# MainMemory.net
KiCad netlist of a schematic drawn in EAGLE
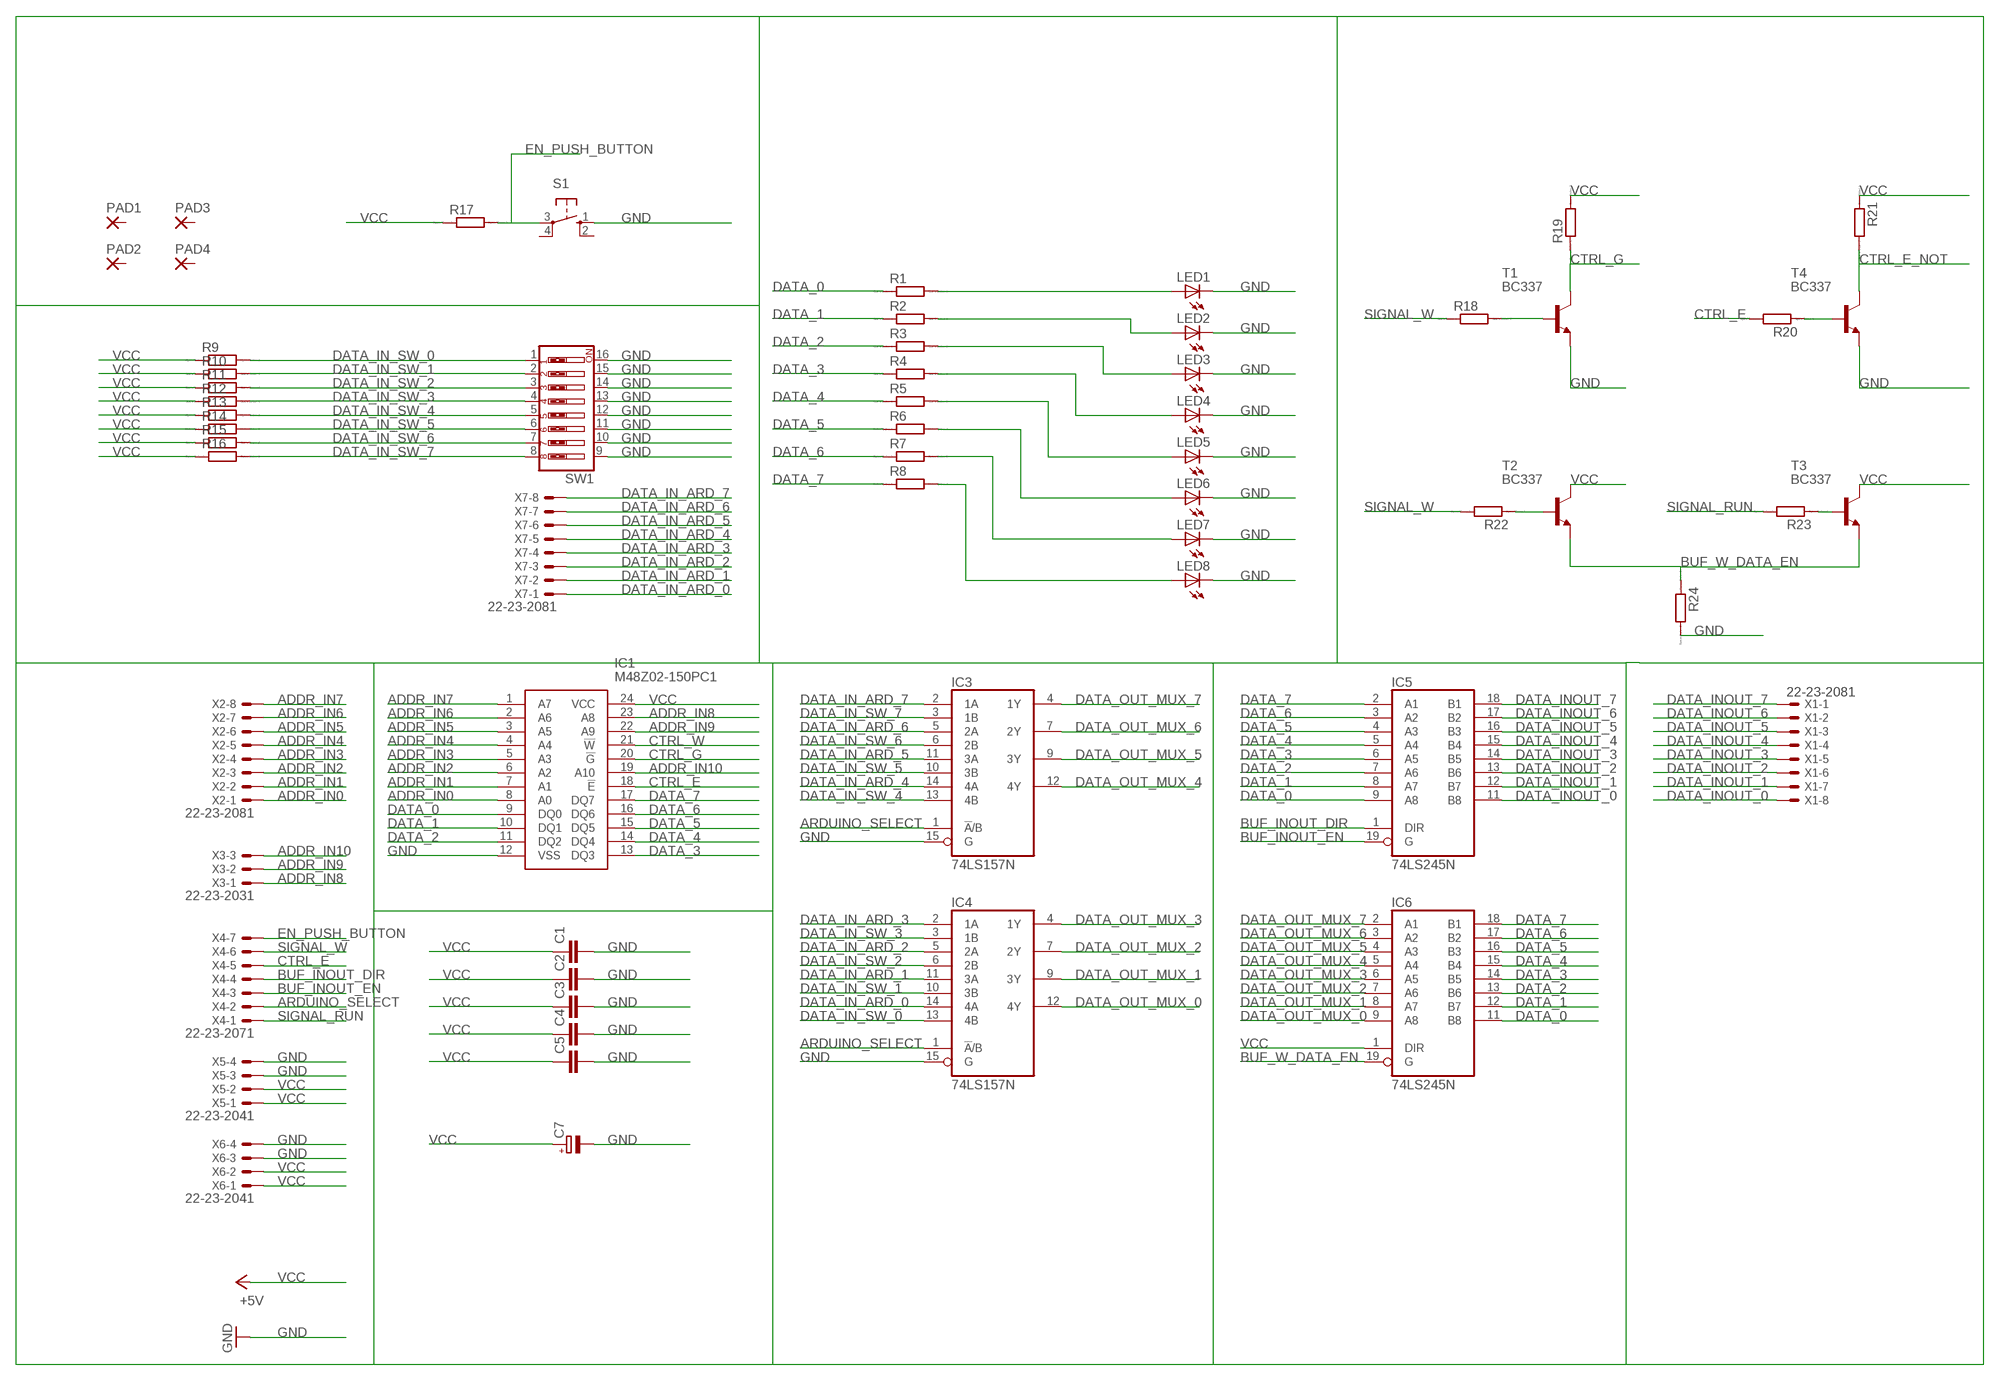
[diagram p0: schematic, sheet 1]

(export (version "E")
  (design (tool "Eeschema 10.0.6"))
  (components
    (comp (ref "C1")
      (value "C-EU025-025X050")
      (footprint "eagle-import:C025-025X050")
      (libsource (lib "eagle-import") (part "C-EU025-025X050"))
    )
    (comp (ref "C2")
      (value "C-EU025-025X050")
      (footprint "eagle-import:C025-025X050")
      (libsource (lib "eagle-import") (part "C-EU025-025X050"))
    )
    (comp (ref "C3")
      (value "C-EU025-025X050")
      (footprint "eagle-import:C025-025X050")
      (libsource (lib "eagle-import") (part "C-EU025-025X050"))
    )
    (comp (ref "C4")
      (value "C-EU025-025X050")
      (footprint "eagle-import:C025-025X050")
      (libsource (lib "eagle-import") (part "C-EU025-025X050"))
    )
    (comp (ref "C5")
      (value "C-EU025-025X050")
      (footprint "eagle-import:C025-025X050")
      (libsource (lib "eagle-import") (part "C-EU025-025X050"))
    )
    (comp (ref "C7")
      (value "CPOL-EUE2.5-6")
      (footprint "eagle-import:E2,5-6")
      (libsource (lib "eagle-import") (part "CPOL-EUE2.5-6"))
    )
    (comp (ref "IC1")
      (value "M48Z02-150PC1")
      (footprint "eagle-import:DIP1562W53P279L3454H965Q24N")
      (fields (field (name "MOUSER_PART_NUMBER") "511-M48Z0215PC1") (field (name "RS_PART_NUMBER") "8289958"))
      (libsource (lib "eagle-import") (part "M48Z02-150PC1"))
    )
    (comp (ref "IC3")
      (value "74LS157N")
      (footprint "eagle-import:DIL16")
      (libsource (lib "eagle-import") (part "74157NLS"))
    )
    (comp (ref "IC4")
      (value "74LS157N")
      (footprint "eagle-import:DIL16")
      (libsource (lib "eagle-import") (part "74157NLS"))
    )
    (comp (ref "IC5")
      (value "74LS245N")
      (footprint "eagle-import:DIL20")
      (libsource (lib "eagle-import") (part "74245NLS"))
    )
    (comp (ref "IC6")
      (value "74LS245N")
      (footprint "eagle-import:DIL20")
      (libsource (lib "eagle-import") (part "74245NLS"))
    )
    (comp (ref "LED1")
      (value "LED5MM")
      (footprint "eagle-import:LED5MM")
      (libsource (lib "eagle-import") (part "LED5MM"))
    )
    (comp (ref "LED2")
      (value "LED5MM")
      (footprint "eagle-import:LED5MM")
      (libsource (lib "eagle-import") (part "LED5MM"))
    )
    (comp (ref "LED3")
      (value "LED5MM")
      (footprint "eagle-import:LED5MM")
      (libsource (lib "eagle-import") (part "LED5MM"))
    )
    (comp (ref "LED4")
      (value "LED5MM")
      (footprint "eagle-import:LED5MM")
      (libsource (lib "eagle-import") (part "LED5MM"))
    )
    (comp (ref "LED5")
      (value "LED5MM")
      (footprint "eagle-import:LED5MM")
      (libsource (lib "eagle-import") (part "LED5MM"))
    )
    (comp (ref "LED6")
      (value "LED5MM")
      (footprint "eagle-import:LED5MM")
      (libsource (lib "eagle-import") (part "LED5MM"))
    )
    (comp (ref "LED7")
      (value "LED5MM")
      (footprint "eagle-import:LED5MM")
      (libsource (lib "eagle-import") (part "LED5MM"))
    )
    (comp (ref "LED8")
      (value "LED5MM")
      (footprint "eagle-import:LED5MM")
      (libsource (lib "eagle-import") (part "LED5MM"))
    )
    (comp (ref "PAD1")
      (value "3,17/1,3")
      (footprint "eagle-import:3,17_1,3")
      (libsource (lib "eagle-import") (part "3,17/1,3"))
    )
    (comp (ref "PAD2")
      (value "3,17/1,3")
      (footprint "eagle-import:3,17_1,3")
      (libsource (lib "eagle-import") (part "3,17/1,3"))
    )
    (comp (ref "PAD3")
      (value "3,17/1,3")
      (footprint "eagle-import:3,17_1,3")
      (libsource (lib "eagle-import") (part "3,17/1,3"))
    )
    (comp (ref "PAD4")
      (value "3,17/1,3")
      (footprint "eagle-import:3,17_1,3")
      (libsource (lib "eagle-import") (part "3,17/1,3"))
    )
    (comp (ref "R1")
      (value "R0207/10")
      (footprint "eagle-import:0207_10")
      (libsource (lib "eagle-import") (part "R0207/10"))
    )
    (comp (ref "R2")
      (value "R0207/10")
      (footprint "eagle-import:0207_10")
      (libsource (lib "eagle-import") (part "R0207/10"))
    )
    (comp (ref "R3")
      (value "R0207/10")
      (footprint "eagle-import:0207_10")
      (libsource (lib "eagle-import") (part "R0207/10"))
    )
    (comp (ref "R4")
      (value "R0207/10")
      (footprint "eagle-import:0207_10")
      (libsource (lib "eagle-import") (part "R0207/10"))
    )
    (comp (ref "R5")
      (value "R0207/10")
      (footprint "eagle-import:0207_10")
      (libsource (lib "eagle-import") (part "R0207/10"))
    )
    (comp (ref "R6")
      (value "R0207/10")
      (footprint "eagle-import:0207_10")
      (libsource (lib "eagle-import") (part "R0207/10"))
    )
    (comp (ref "R7")
      (value "R0207/10")
      (footprint "eagle-import:0207_10")
      (libsource (lib "eagle-import") (part "R0207/10"))
    )
    (comp (ref "R8")
      (value "R0207/10")
      (footprint "eagle-import:0207_10")
      (libsource (lib "eagle-import") (part "R0207/10"))
    )
    (comp (ref "R9")
      (value "R0207/10")
      (footprint "eagle-import:0207_10")
      (libsource (lib "eagle-import") (part "R0207/10"))
    )
    (comp (ref "R10")
      (value "R0207/10")
      (footprint "eagle-import:0207_10")
      (libsource (lib "eagle-import") (part "R0207/10"))
    )
    (comp (ref "R11")
      (value "R0207/10")
      (footprint "eagle-import:0207_10")
      (libsource (lib "eagle-import") (part "R0207/10"))
    )
    (comp (ref "R12")
      (value "R0207/10")
      (footprint "eagle-import:0207_10")
      (libsource (lib "eagle-import") (part "R0207/10"))
    )
    (comp (ref "R13")
      (value "R0207/10")
      (footprint "eagle-import:0207_10")
      (libsource (lib "eagle-import") (part "R0207/10"))
    )
    (comp (ref "R14")
      (value "R0207/10")
      (footprint "eagle-import:0207_10")
      (libsource (lib "eagle-import") (part "R0207/10"))
    )
    (comp (ref "R15")
      (value "R0207/10")
      (footprint "eagle-import:0207_10")
      (libsource (lib "eagle-import") (part "R0207/10"))
    )
    (comp (ref "R16")
      (value "R0207/10")
      (footprint "eagle-import:0207_10")
      (libsource (lib "eagle-import") (part "R0207/10"))
    )
    (comp (ref "R17")
      (value "R0207/10")
      (footprint "eagle-import:0207_10")
      (libsource (lib "eagle-import") (part "R0207/10"))
    )
    (comp (ref "R18")
      (value "R0207/10")
      (footprint "eagle-import:0207_10")
      (libsource (lib "eagle-import") (part "R0207/10"))
    )
    (comp (ref "R19")
      (value "R0207/10")
      (footprint "eagle-import:0207_10")
      (libsource (lib "eagle-import") (part "R0207/10"))
    )
    (comp (ref "R20")
      (value "R0207/10")
      (footprint "eagle-import:0207_10")
      (libsource (lib "eagle-import") (part "R0207/10"))
    )
    (comp (ref "R21")
      (value "R0207/10")
      (footprint "eagle-import:0207_10")
      (libsource (lib "eagle-import") (part "R0207/10"))
    )
    (comp (ref "R22")
      (value "R0207/10")
      (footprint "eagle-import:0207_10")
      (libsource (lib "eagle-import") (part "R0207/10"))
    )
    (comp (ref "R23")
      (value "R0207/10")
      (footprint "eagle-import:0207_10")
      (libsource (lib "eagle-import") (part "R0207/10"))
    )
    (comp (ref "R24")
      (value "R0207/10")
      (footprint "eagle-import:0207_10")
      (libsource (lib "eagle-import") (part "R0207/10"))
    )
    (comp (ref "S1")
      (value "10-XX")
      (footprint "eagle-import:B3F-10XX")
      (fields (field (name "MPN") "B3F-1000"))
      (libsource (lib "eagle-import") (part "10-XX"))
    )
    (comp (ref "SW1")
      (value "SW_DIP-8")
      (footprint "eagle-import:EDG-08")
      (libsource (lib "eagle-import") (part "SW_DIP-8"))
    )
    (comp (ref "T1")
      (value "BC337")
      (footprint "eagle-import:TO92")
      (libsource (lib "eagle-import") (part "BC337"))
    )
    (comp (ref "T2")
      (value "BC337")
      (footprint "eagle-import:TO92")
      (libsource (lib "eagle-import") (part "BC337"))
    )
    (comp (ref "T3")
      (value "BC337")
      (footprint "eagle-import:TO92")
      (libsource (lib "eagle-import") (part "BC337"))
    )
    (comp (ref "T4")
      (value "BC337")
      (footprint "eagle-import:TO92")
      (libsource (lib "eagle-import") (part "BC337"))
    )
    (comp (ref "X1")
      (value "22-23-2081")
      (footprint "eagle-import:22-23-2081")
      (fields (field (name "MF") "MOLEX"))
      (libsource (lib "eagle-import") (part "22-23-2081"))
    )
    (comp (ref "X2")
      (value "22-23-2081")
      (footprint "eagle-import:22-23-2081")
      (fields (field (name "MF") "MOLEX"))
      (libsource (lib "eagle-import") (part "22-23-2081"))
    )
    (comp (ref "X3")
      (value "22-23-2031")
      (footprint "eagle-import:22-23-2031")
      (fields (field (name "MF") "MOLEX"))
      (libsource (lib "eagle-import") (part "22-23-2031"))
    )
    (comp (ref "X4")
      (value "22-23-2071")
      (footprint "eagle-import:22-23-2071")
      (fields (field (name "MF") "MOLEX"))
      (libsource (lib "eagle-import") (part "22-23-2071"))
    )
    (comp (ref "X5")
      (value "22-23-2041")
      (footprint "eagle-import:22-23-2041")
      (fields (field (name "MF") "MOLEX"))
      (libsource (lib "eagle-import") (part "22-23-2041"))
    )
    (comp (ref "X6")
      (value "22-23-2041")
      (footprint "eagle-import:22-23-2041")
      (fields (field (name "MF") "MOLEX"))
      (libsource (lib "eagle-import") (part "22-23-2041"))
    )
    (comp (ref "X7")
      (value "22-23-2081")
      (footprint "eagle-import:22-23-2081")
      (fields (field (name "MF") "MOLEX"))
      (libsource (lib "eagle-import") (part "22-23-2081"))
    )
  )
  (nets
    (net (code "1") (name "+5V") (class "Default")
      (node (ref "C1") (pin "1") (pinfunction "1_1") (pintype "passive"))
      (node (ref "C2") (pin "1") (pinfunction "1_1") (pintype "passive"))
      (node (ref "C3") (pin "1") (pinfunction "1_1") (pintype "passive"))
      (node (ref "C4") (pin "1") (pinfunction "1_1") (pintype "passive"))
      (node (ref "C5") (pin "1") (pinfunction "1_1") (pintype "passive"))
      (node (ref "C7") (pin "+") (pinfunction "+_+") (pintype "passive"))
      (node (ref "IC1") (pin "24") (pinfunction "VCC_24") (pintype "power_in"))
      (node (ref "IC6") (pin "1") (pinfunction "DIR_1") (pintype "input"))
      (node (ref "R10") (pin "1") (pinfunction "1_1") (pintype "passive"))
      (node (ref "R11") (pin "1") (pinfunction "1_1") (pintype "passive"))
      (node (ref "R12") (pin "1") (pinfunction "1_1") (pintype "passive"))
      (node (ref "R13") (pin "1") (pinfunction "1_1") (pintype "passive"))
      (node (ref "R14") (pin "1") (pinfunction "1_1") (pintype "passive"))
      (node (ref "R15") (pin "1") (pinfunction "1_1") (pintype "passive"))
      (node (ref "R16") (pin "1") (pinfunction "1_1") (pintype "passive"))
      (node (ref "R17") (pin "1") (pinfunction "1_1") (pintype "passive"))
      (node (ref "R19") (pin "2") (pinfunction "2_2") (pintype "passive"))
      (node (ref "R21") (pin "1") (pinfunction "1_1") (pintype "passive"))
      (node (ref "R9") (pin "1") (pinfunction "1_1") (pintype "passive"))
      (node (ref "T2") (pin "3") (pinfunction "C_3") (pintype "passive"))
      (node (ref "T3") (pin "3") (pinfunction "C_3") (pintype "passive"))
      (node (ref "X5") (pin "1") (pinfunction "S_1") (pintype "passive"))
      (node (ref "X5") (pin "2") (pinfunction "S_2") (pintype "passive"))
      (node (ref "X6") (pin "1") (pinfunction "S_1") (pintype "passive"))
      (node (ref "X6") (pin "2") (pinfunction "S_2") (pintype "passive"))
    )
    (net (code "2") (name "/ADDR_IN0") (class "Default")
      (node (ref "IC1") (pin "8") (pinfunction "A0_8") (pintype "bidirectional"))
      (node (ref "X2") (pin "1") (pinfunction "S_1") (pintype "passive"))
    )
    (net (code "3") (name "/ADDR_IN1") (class "Default")
      (node (ref "IC1") (pin "7") (pinfunction "A1_7") (pintype "bidirectional"))
      (node (ref "X2") (pin "2") (pinfunction "S_2") (pintype "passive"))
    )
    (net (code "4") (name "/ADDR_IN2") (class "Default")
      (node (ref "IC1") (pin "6") (pinfunction "A2_6") (pintype "bidirectional"))
      (node (ref "X2") (pin "3") (pinfunction "S_3") (pintype "passive"))
    )
    (net (code "5") (name "/ADDR_IN3") (class "Default")
      (node (ref "IC1") (pin "5") (pinfunction "A3_5") (pintype "bidirectional"))
      (node (ref "X2") (pin "4") (pinfunction "S_4") (pintype "passive"))
    )
    (net (code "6") (name "/ADDR_IN4") (class "Default")
      (node (ref "IC1") (pin "4") (pinfunction "A4_4") (pintype "bidirectional"))
      (node (ref "X2") (pin "5") (pinfunction "S_5") (pintype "passive"))
    )
    (net (code "7") (name "/ADDR_IN5") (class "Default")
      (node (ref "IC1") (pin "3") (pinfunction "A5_3") (pintype "bidirectional"))
      (node (ref "X2") (pin "6") (pinfunction "S_6") (pintype "passive"))
    )
    (net (code "8") (name "/ADDR_IN6") (class "Default")
      (node (ref "IC1") (pin "2") (pinfunction "A6_2") (pintype "bidirectional"))
      (node (ref "X2") (pin "7") (pinfunction "S_7") (pintype "passive"))
    )
    (net (code "9") (name "/ADDR_IN7") (class "Default")
      (node (ref "IC1") (pin "1") (pinfunction "A7_1") (pintype "bidirectional"))
      (node (ref "X2") (pin "8") (pinfunction "S_8") (pintype "passive"))
    )
    (net (code "10") (name "/ADDR_IN8") (class "Default")
      (node (ref "IC1") (pin "23") (pinfunction "A8_23") (pintype "bidirectional"))
      (node (ref "X3") (pin "1") (pinfunction "S_1") (pintype "passive"))
    )
    (net (code "11") (name "/ADDR_IN9") (class "Default")
      (node (ref "IC1") (pin "22") (pinfunction "A9_22") (pintype "bidirectional"))
      (node (ref "X3") (pin "2") (pinfunction "S_2") (pintype "passive"))
    )
    (net (code "12") (name "/ADDR_IN10") (class "Default")
      (node (ref "IC1") (pin "19") (pinfunction "A10_19") (pintype "bidirectional"))
      (node (ref "X3") (pin "3") (pinfunction "S_3") (pintype "passive"))
    )
    (net (code "13") (name "/ARDUINO_SELECT") (class "Default")
      (node (ref "IC3") (pin "1") (pinfunction "~{A}/B_1") (pintype "input"))
      (node (ref "IC4") (pin "1") (pinfunction "~{A}/B_1") (pintype "input"))
      (node (ref "X4") (pin "2") (pinfunction "S_2") (pintype "passive"))
    )
    (net (code "14") (name "/BUF_INOUT_DIR") (class "Default")
      (node (ref "IC5") (pin "1") (pinfunction "DIR_1") (pintype "input"))
      (node (ref "X4") (pin "4") (pinfunction "S_4") (pintype "passive"))
    )
    (net (code "15") (name "/BUF_INOUT_EN") (class "Default")
      (node (ref "IC5") (pin "19") (pinfunction "G_19") (pintype "input"))
      (node (ref "X4") (pin "3") (pinfunction "S_3") (pintype "passive"))
    )
    (net (code "16") (name "/BUF_W_DATA_EN") (class "Default")
      (node (ref "IC6") (pin "19") (pinfunction "G_19") (pintype "input"))
      (node (ref "R24") (pin "1") (pinfunction "1_1") (pintype "passive"))
      (node (ref "T2") (pin "1") (pinfunction "E_1") (pintype "passive"))
      (node (ref "T3") (pin "1") (pinfunction "E_1") (pintype "passive"))
    )
    (net (code "17") (name "/CTRL_E") (class "Default")
      (node (ref "IC1") (pin "18") (pinfunction "~{E}_18") (pintype "bidirectional"))
      (node (ref "R20") (pin "2") (pinfunction "2_2") (pintype "passive"))
      (node (ref "X4") (pin "5") (pinfunction "S_5") (pintype "passive"))
    )
    (net (code "18") (name "/CTRL_E_NOT") (class "Default")
      (node (ref "R21") (pin "2") (pinfunction "2_2") (pintype "passive"))
      (node (ref "T4") (pin "3") (pinfunction "C_3") (pintype "passive"))
    )
    (net (code "19") (name "/CTRL_G") (class "Default")
      (node (ref "IC1") (pin "20") (pinfunction "~{G}_20") (pintype "bidirectional"))
      (node (ref "R19") (pin "1") (pinfunction "1_1") (pintype "passive"))
      (node (ref "T1") (pin "3") (pinfunction "C_3") (pintype "passive"))
    )
    (net (code "20") (name "/CTRL_W") (class "Default")
      (node (ref "IC1") (pin "21") (pinfunction "~{W}_21") (pintype "bidirectional"))
    )
    (net (code "21") (name "/DATA_0") (class "Default")
      (node (ref "IC1") (pin "9") (pinfunction "DQ0_9") (pintype "bidirectional"))
      (node (ref "IC5") (pin "9") (pinfunction "A8_9") (pintype "bidirectional"))
      (node (ref "IC6") (pin "11") (pinfunction "B8_11") (pintype "bidirectional"))
      (node (ref "R1") (pin "1") (pinfunction "1_1") (pintype "passive"))
    )
    (net (code "22") (name "/DATA_1") (class "Default")
      (node (ref "IC1") (pin "10") (pinfunction "DQ1_10") (pintype "bidirectional"))
      (node (ref "IC5") (pin "8") (pinfunction "A7_8") (pintype "bidirectional"))
      (node (ref "IC6") (pin "12") (pinfunction "B7_12") (pintype "bidirectional"))
      (node (ref "R2") (pin "1") (pinfunction "1_1") (pintype "passive"))
    )
    (net (code "23") (name "/DATA_2") (class "Default")
      (node (ref "IC1") (pin "11") (pinfunction "DQ2_11") (pintype "bidirectional"))
      (node (ref "IC5") (pin "7") (pinfunction "A6_7") (pintype "bidirectional"))
      (node (ref "IC6") (pin "13") (pinfunction "B6_13") (pintype "bidirectional"))
      (node (ref "R3") (pin "1") (pinfunction "1_1") (pintype "passive"))
    )
    (net (code "24") (name "/DATA_3") (class "Default")
      (node (ref "IC1") (pin "13") (pinfunction "DQ3_13") (pintype "bidirectional"))
      (node (ref "IC5") (pin "6") (pinfunction "A5_6") (pintype "bidirectional"))
      (node (ref "IC6") (pin "14") (pinfunction "B5_14") (pintype "bidirectional"))
      (node (ref "R4") (pin "1") (pinfunction "1_1") (pintype "passive"))
    )
    (net (code "25") (name "/DATA_4") (class "Default")
      (node (ref "IC1") (pin "14") (pinfunction "DQ4_14") (pintype "bidirectional"))
      (node (ref "IC5") (pin "5") (pinfunction "A4_5") (pintype "bidirectional"))
      (node (ref "IC6") (pin "15") (pinfunction "B4_15") (pintype "bidirectional"))
      (node (ref "R5") (pin "1") (pinfunction "1_1") (pintype "passive"))
    )
    (net (code "26") (name "/DATA_5") (class "Default")
      (node (ref "IC1") (pin "15") (pinfunction "DQ5_15") (pintype "bidirectional"))
      (node (ref "IC5") (pin "4") (pinfunction "A3_4") (pintype "bidirectional"))
      (node (ref "IC6") (pin "16") (pinfunction "B3_16") (pintype "bidirectional"))
      (node (ref "R6") (pin "1") (pinfunction "1_1") (pintype "passive"))
    )
    (net (code "27") (name "/DATA_6") (class "Default")
      (node (ref "IC1") (pin "16") (pinfunction "DQ6_16") (pintype "bidirectional"))
      (node (ref "IC5") (pin "3") (pinfunction "A2_3") (pintype "bidirectional"))
      (node (ref "IC6") (pin "17") (pinfunction "B2_17") (pintype "bidirectional"))
      (node (ref "R7") (pin "1") (pinfunction "1_1") (pintype "passive"))
    )
    (net (code "28") (name "/DATA_7") (class "Default")
      (node (ref "IC1") (pin "17") (pinfunction "DQ7_17") (pintype "bidirectional"))
      (node (ref "IC5") (pin "2") (pinfunction "A1_2") (pintype "bidirectional"))
      (node (ref "IC6") (pin "18") (pinfunction "B1_18") (pintype "bidirectional"))
      (node (ref "R8") (pin "1") (pinfunction "1_1") (pintype "passive"))
    )
    (net (code "29") (name "/DATA_INOUT_0") (class "Default")
      (node (ref "IC5") (pin "11") (pinfunction "B8_11") (pintype "bidirectional"))
      (node (ref "X1") (pin "8") (pinfunction "S_8") (pintype "passive"))
    )
    (net (code "30") (name "/DATA_INOUT_1") (class "Default")
      (node (ref "IC5") (pin "12") (pinfunction "B7_12") (pintype "bidirectional"))
      (node (ref "X1") (pin "7") (pinfunction "S_7") (pintype "passive"))
    )
    (net (code "31") (name "/DATA_INOUT_2") (class "Default")
      (node (ref "IC5") (pin "13") (pinfunction "B6_13") (pintype "bidirectional"))
      (node (ref "X1") (pin "6") (pinfunction "S_6") (pintype "passive"))
    )
    (net (code "32") (name "/DATA_INOUT_3") (class "Default")
      (node (ref "IC5") (pin "14") (pinfunction "B5_14") (pintype "bidirectional"))
      (node (ref "X1") (pin "5") (pinfunction "S_5") (pintype "passive"))
    )
    (net (code "33") (name "/DATA_INOUT_4") (class "Default")
      (node (ref "IC5") (pin "15") (pinfunction "B4_15") (pintype "bidirectional"))
      (node (ref "X1") (pin "4") (pinfunction "S_4") (pintype "passive"))
    )
    (net (code "34") (name "/DATA_INOUT_5") (class "Default")
      (node (ref "IC5") (pin "16") (pinfunction "B3_16") (pintype "bidirectional"))
      (node (ref "X1") (pin "3") (pinfunction "S_3") (pintype "passive"))
    )
    (net (code "35") (name "/DATA_INOUT_6") (class "Default")
      (node (ref "IC5") (pin "17") (pinfunction "B2_17") (pintype "bidirectional"))
      (node (ref "X1") (pin "2") (pinfunction "S_2") (pintype "passive"))
    )
    (net (code "36") (name "/DATA_INOUT_7") (class "Default")
      (node (ref "IC5") (pin "18") (pinfunction "B1_18") (pintype "bidirectional"))
      (node (ref "X1") (pin "1") (pinfunction "S_1") (pintype "passive"))
    )
    (net (code "37") (name "/DATA_IN_ARD_0") (class "Default")
      (node (ref "IC4") (pin "14") (pinfunction "4A_14") (pintype "input"))
      (node (ref "X7") (pin "1") (pinfunction "S_1") (pintype "passive"))
    )
    (net (code "38") (name "/DATA_IN_ARD_1") (class "Default")
      (node (ref "IC4") (pin "11") (pinfunction "3A_11") (pintype "input"))
      (node (ref "X7") (pin "2") (pinfunction "S_2") (pintype "passive"))
    )
    (net (code "39") (name "/DATA_IN_ARD_2") (class "Default")
      (node (ref "IC4") (pin "5") (pinfunction "2A_5") (pintype "input"))
      (node (ref "X7") (pin "3") (pinfunction "S_3") (pintype "passive"))
    )
    (net (code "40") (name "/DATA_IN_ARD_3") (class "Default")
      (node (ref "IC4") (pin "2") (pinfunction "1A_2") (pintype "input"))
      (node (ref "X7") (pin "4") (pinfunction "S_4") (pintype "passive"))
    )
    (net (code "41") (name "/DATA_IN_ARD_4") (class "Default")
      (node (ref "IC3") (pin "14") (pinfunction "4A_14") (pintype "input"))
      (node (ref "X7") (pin "5") (pinfunction "S_5") (pintype "passive"))
    )
    (net (code "42") (name "/DATA_IN_ARD_5") (class "Default")
      (node (ref "IC3") (pin "11") (pinfunction "3A_11") (pintype "input"))
      (node (ref "X7") (pin "6") (pinfunction "S_6") (pintype "passive"))
    )
    (net (code "43") (name "/DATA_IN_ARD_6") (class "Default")
      (node (ref "IC3") (pin "5") (pinfunction "2A_5") (pintype "input"))
      (node (ref "X7") (pin "7") (pinfunction "S_7") (pintype "passive"))
    )
    (net (code "44") (name "/DATA_IN_ARD_7") (class "Default")
      (node (ref "IC3") (pin "2") (pinfunction "1A_2") (pintype "input"))
      (node (ref "X7") (pin "8") (pinfunction "S_8") (pintype "passive"))
    )
    (net (code "45") (name "/DATA_IN_SW_0") (class "Default")
      (node (ref "IC4") (pin "13") (pinfunction "4B_13") (pintype "input"))
      (node (ref "R9") (pin "2") (pinfunction "2_2") (pintype "passive"))
      (node (ref "SW1") (pin "1") (pinfunction "1_1") (pintype "passive"))
    )
    (net (code "46") (name "/DATA_IN_SW_1") (class "Default")
      (node (ref "IC4") (pin "10") (pinfunction "3B_10") (pintype "input"))
      (node (ref "R10") (pin "2") (pinfunction "2_2") (pintype "passive"))
      (node (ref "SW1") (pin "2") (pinfunction "2_2") (pintype "passive"))
    )
    (net (code "47") (name "/DATA_IN_SW_2") (class "Default")
      (node (ref "IC4") (pin "6") (pinfunction "2B_6") (pintype "input"))
      (node (ref "R11") (pin "2") (pinfunction "2_2") (pintype "passive"))
      (node (ref "SW1") (pin "3") (pinfunction "3_3") (pintype "passive"))
    )
    (net (code "48") (name "/DATA_IN_SW_3") (class "Default")
      (node (ref "IC4") (pin "3") (pinfunction "1B_3") (pintype "input"))
      (node (ref "R12") (pin "2") (pinfunction "2_2") (pintype "passive"))
      (node (ref "SW1") (pin "4") (pinfunction "4_4") (pintype "passive"))
    )
    (net (code "49") (name "/DATA_IN_SW_4") (class "Default")
      (node (ref "IC3") (pin "13") (pinfunction "4B_13") (pintype "input"))
      (node (ref "R13") (pin "2") (pinfunction "2_2") (pintype "passive"))
      (node (ref "SW1") (pin "5") (pinfunction "5_5") (pintype "passive"))
    )
    (net (code "50") (name "/DATA_IN_SW_5") (class "Default")
      (node (ref "IC3") (pin "10") (pinfunction "3B_10") (pintype "input"))
      (node (ref "R14") (pin "2") (pinfunction "2_2") (pintype "passive"))
      (node (ref "SW1") (pin "6") (pinfunction "6_6") (pintype "passive"))
    )
    (net (code "51") (name "/DATA_IN_SW_6") (class "Default")
      (node (ref "IC3") (pin "6") (pinfunction "2B_6") (pintype "input"))
      (node (ref "R15") (pin "2") (pinfunction "2_2") (pintype "passive"))
      (node (ref "SW1") (pin "7") (pinfunction "7_7") (pintype "passive"))
    )
    (net (code "52") (name "/DATA_IN_SW_7") (class "Default")
      (node (ref "IC3") (pin "3") (pinfunction "1B_3") (pintype "input"))
      (node (ref "R16") (pin "2") (pinfunction "2_2") (pintype "passive"))
      (node (ref "SW1") (pin "8") (pinfunction "8_8") (pintype "passive"))
    )
    (net (code "53") (name "/DATA_OUT_MUX_0") (class "Default")
      (node (ref "IC4") (pin "12") (pinfunction "4Y_12") (pintype "output"))
      (node (ref "IC6") (pin "9") (pinfunction "A8_9") (pintype "bidirectional"))
    )
    (net (code "54") (name "/DATA_OUT_MUX_1") (class "Default")
      (node (ref "IC4") (pin "9") (pinfunction "3Y_9") (pintype "output"))
      (node (ref "IC6") (pin "8") (pinfunction "A7_8") (pintype "bidirectional"))
    )
    (net (code "55") (name "/DATA_OUT_MUX_2") (class "Default")
      (node (ref "IC4") (pin "7") (pinfunction "2Y_7") (pintype "output"))
      (node (ref "IC6") (pin "7") (pinfunction "A6_7") (pintype "bidirectional"))
    )
    (net (code "56") (name "/DATA_OUT_MUX_3") (class "Default")
      (node (ref "IC4") (pin "4") (pinfunction "1Y_4") (pintype "output"))
      (node (ref "IC6") (pin "6") (pinfunction "A5_6") (pintype "bidirectional"))
    )
    (net (code "57") (name "/DATA_OUT_MUX_4") (class "Default")
      (node (ref "IC3") (pin "12") (pinfunction "4Y_12") (pintype "output"))
      (node (ref "IC6") (pin "5") (pinfunction "A4_5") (pintype "bidirectional"))
    )
    (net (code "58") (name "/DATA_OUT_MUX_5") (class "Default")
      (node (ref "IC3") (pin "9") (pinfunction "3Y_9") (pintype "output"))
      (node (ref "IC6") (pin "4") (pinfunction "A3_4") (pintype "bidirectional"))
    )
    (net (code "59") (name "/DATA_OUT_MUX_6") (class "Default")
      (node (ref "IC3") (pin "7") (pinfunction "2Y_7") (pintype "output"))
      (node (ref "IC6") (pin "3") (pinfunction "A2_3") (pintype "bidirectional"))
    )
    (net (code "60") (name "/DATA_OUT_MUX_7") (class "Default")
      (node (ref "IC3") (pin "4") (pinfunction "1Y_4") (pintype "output"))
      (node (ref "IC6") (pin "2") (pinfunction "A1_2") (pintype "bidirectional"))
    )
    (net (code "61") (name "/EN_PUSH_BUTTON") (class "Default")
      (node (ref "R17") (pin "2") (pinfunction "2_2") (pintype "passive"))
      (node (ref "S1") (pin "3") (pinfunction "P_3") (pintype "passive"))
      (node (ref "X4") (pin "7") (pinfunction "S_7") (pintype "passive"))
    )
    (net (code "62") (name "/SIGNAL_RUN") (class "Default")
      (node (ref "R23") (pin "2") (pinfunction "2_2") (pintype "passive"))
      (node (ref "X4") (pin "1") (pinfunction "S_1") (pintype "passive"))
    )
    (net (code "63") (name "/SIGNAL_W") (class "Default")
      (node (ref "R18") (pin "1") (pinfunction "1_1") (pintype "passive"))
      (node (ref "R22") (pin "2") (pinfunction "2_2") (pintype "passive"))
      (node (ref "X4") (pin "6") (pinfunction "S_6") (pintype "passive"))
    )
    (net (code "64") (name "GND") (class "Default")
      (node (ref "C1") (pin "2") (pinfunction "2_2") (pintype "passive"))
      (node (ref "C2") (pin "2") (pinfunction "2_2") (pintype "passive"))
      (node (ref "C3") (pin "2") (pinfunction "2_2") (pintype "passive"))
      (node (ref "C4") (pin "2") (pinfunction "2_2") (pintype "passive"))
      (node (ref "C5") (pin "2") (pinfunction "2_2") (pintype "passive"))
      (node (ref "C7") (pin "-") (pinfunction "-_-") (pintype "passive"))
      (node (ref "IC1") (pin "12") (pinfunction "VSS_12") (pintype "power_in"))
      (node (ref "IC3") (pin "15") (pinfunction "G_15") (pintype "input"))
      (node (ref "IC4") (pin "15") (pinfunction "G_15") (pintype "input"))
      (node (ref "LED1") (pin "K") (pinfunction "C_K") (pintype "passive"))
      (node (ref "LED2") (pin "K") (pinfunction "C_K") (pintype "passive"))
      (node (ref "LED3") (pin "K") (pinfunction "C_K") (pintype "passive"))
      (node (ref "LED4") (pin "K") (pinfunction "C_K") (pintype "passive"))
      (node (ref "LED5") (pin "K") (pinfunction "C_K") (pintype "passive"))
      (node (ref "LED6") (pin "K") (pinfunction "C_K") (pintype "passive"))
      (node (ref "LED7") (pin "K") (pinfunction "C_K") (pintype "passive"))
      (node (ref "LED8") (pin "K") (pinfunction "C_K") (pintype "passive"))
      (node (ref "R24") (pin "2") (pinfunction "2_2") (pintype "passive"))
      (node (ref "S1") (pin "1") (pinfunction "S_1") (pintype "passive"))
      (node (ref "SW1") (pin "10") (pinfunction "10_10") (pintype "passive"))
      (node (ref "SW1") (pin "11") (pinfunction "11_11") (pintype "passive"))
      (node (ref "SW1") (pin "12") (pinfunction "12_12") (pintype "passive"))
      (node (ref "SW1") (pin "13") (pinfunction "13_13") (pintype "passive"))
      (node (ref "SW1") (pin "14") (pinfunction "14_14") (pintype "passive"))
      (node (ref "SW1") (pin "15") (pinfunction "15_15") (pintype "passive"))
      (node (ref "SW1") (pin "16") (pinfunction "16_16") (pintype "passive"))
      (node (ref "SW1") (pin "9") (pinfunction "9_9") (pintype "passive"))
      (node (ref "T1") (pin "1") (pinfunction "E_1") (pintype "passive"))
      (node (ref "T4") (pin "1") (pinfunction "E_1") (pintype "passive"))
      (node (ref "X5") (pin "3") (pinfunction "S_3") (pintype "passive"))
      (node (ref "X5") (pin "4") (pinfunction "S_4") (pintype "passive"))
      (node (ref "X6") (pin "3") (pinfunction "S_3") (pintype "passive"))
      (node (ref "X6") (pin "4") (pinfunction "S_4") (pintype "passive"))
    )
    (net (code "65") (name "Net-(LED1-PadA)") (class "Default")
      (node (ref "LED1") (pin "A") (pinfunction "A_A") (pintype "passive"))
      (node (ref "R1") (pin "2") (pinfunction "2_2") (pintype "passive"))
    )
    (net (code "66") (name "Net-(LED2-PadA)") (class "Default")
      (node (ref "LED2") (pin "A") (pinfunction "A_A") (pintype "passive"))
      (node (ref "R2") (pin "2") (pinfunction "2_2") (pintype "passive"))
    )
    (net (code "67") (name "Net-(LED3-PadA)") (class "Default")
      (node (ref "LED3") (pin "A") (pinfunction "A_A") (pintype "passive"))
      (node (ref "R3") (pin "2") (pinfunction "2_2") (pintype "passive"))
    )
    (net (code "68") (name "Net-(LED4-PadA)") (class "Default")
      (node (ref "LED4") (pin "A") (pinfunction "A_A") (pintype "passive"))
      (node (ref "R4") (pin "2") (pinfunction "2_2") (pintype "passive"))
    )
    (net (code "69") (name "Net-(LED5-PadA)") (class "Default")
      (node (ref "LED5") (pin "A") (pinfunction "A_A") (pintype "passive"))
      (node (ref "R5") (pin "2") (pinfunction "2_2") (pintype "passive"))
    )
    (net (code "70") (name "Net-(LED6-PadA)") (class "Default")
      (node (ref "LED6") (pin "A") (pinfunction "A_A") (pintype "passive"))
      (node (ref "R6") (pin "2") (pinfunction "2_2") (pintype "passive"))
    )
    (net (code "71") (name "Net-(LED7-PadA)") (class "Default")
      (node (ref "LED7") (pin "A") (pinfunction "A_A") (pintype "passive"))
      (node (ref "R7") (pin "2") (pinfunction "2_2") (pintype "passive"))
    )
    (net (code "72") (name "Net-(LED8-PadA)") (class "Default")
      (node (ref "LED8") (pin "A") (pinfunction "A_A") (pintype "passive"))
      (node (ref "R8") (pin "2") (pinfunction "2_2") (pintype "passive"))
    )
    (net (code "73") (name "Net-(T1-B)") (class "Default")
      (node (ref "R18") (pin "2") (pinfunction "2_2") (pintype "passive"))
      (node (ref "T1") (pin "2") (pinfunction "B_2") (pintype "passive"))
    )
    (net (code "74") (name "Net-(T2-B)") (class "Default")
      (node (ref "R22") (pin "1") (pinfunction "1_1") (pintype "passive"))
      (node (ref "T2") (pin "2") (pinfunction "B_2") (pintype "passive"))
    )
    (net (code "75") (name "Net-(T3-B)") (class "Default")
      (node (ref "R23") (pin "1") (pinfunction "1_1") (pintype "passive"))
      (node (ref "T3") (pin "2") (pinfunction "B_2") (pintype "passive"))
    )
    (net (code "76") (name "Net-(T4-B)") (class "Default")
      (node (ref "R20") (pin "1") (pinfunction "1_1") (pintype "passive"))
      (node (ref "T4") (pin "2") (pinfunction "B_2") (pintype "passive"))
    )
    (net (code "77") (name "unconnected-(PAD1-P-Pad1)") (class "Default")
      (node (ref "PAD1") (pin "1") (pinfunction "P_1") (pintype "passive"))
    )
    (net (code "78") (name "unconnected-(PAD2-P-Pad1)") (class "Default")
      (node (ref "PAD2") (pin "1") (pinfunction "P_1") (pintype "passive"))
    )
    (net (code "79") (name "unconnected-(PAD3-P-Pad1)") (class "Default")
      (node (ref "PAD3") (pin "1") (pinfunction "P_1") (pintype "passive"))
    )
    (net (code "80") (name "unconnected-(PAD4-P-Pad1)") (class "Default")
      (node (ref "PAD4") (pin "1") (pinfunction "P_1") (pintype "passive"))
    )
    (net (code "81") (name "unconnected-(S1-P1-Pad4)") (class "Default")
      (node (ref "S1") (pin "4") (pinfunction "P1_4") (pintype "passive"))
    )
    (net (code "82") (name "unconnected-(S1-S1-Pad2)") (class "Default")
      (node (ref "S1") (pin "2") (pinfunction "S1_2") (pintype "passive"))
    )
  )
)
